# gas.net
KiCad netlist of a schematic drawn in EAGLE
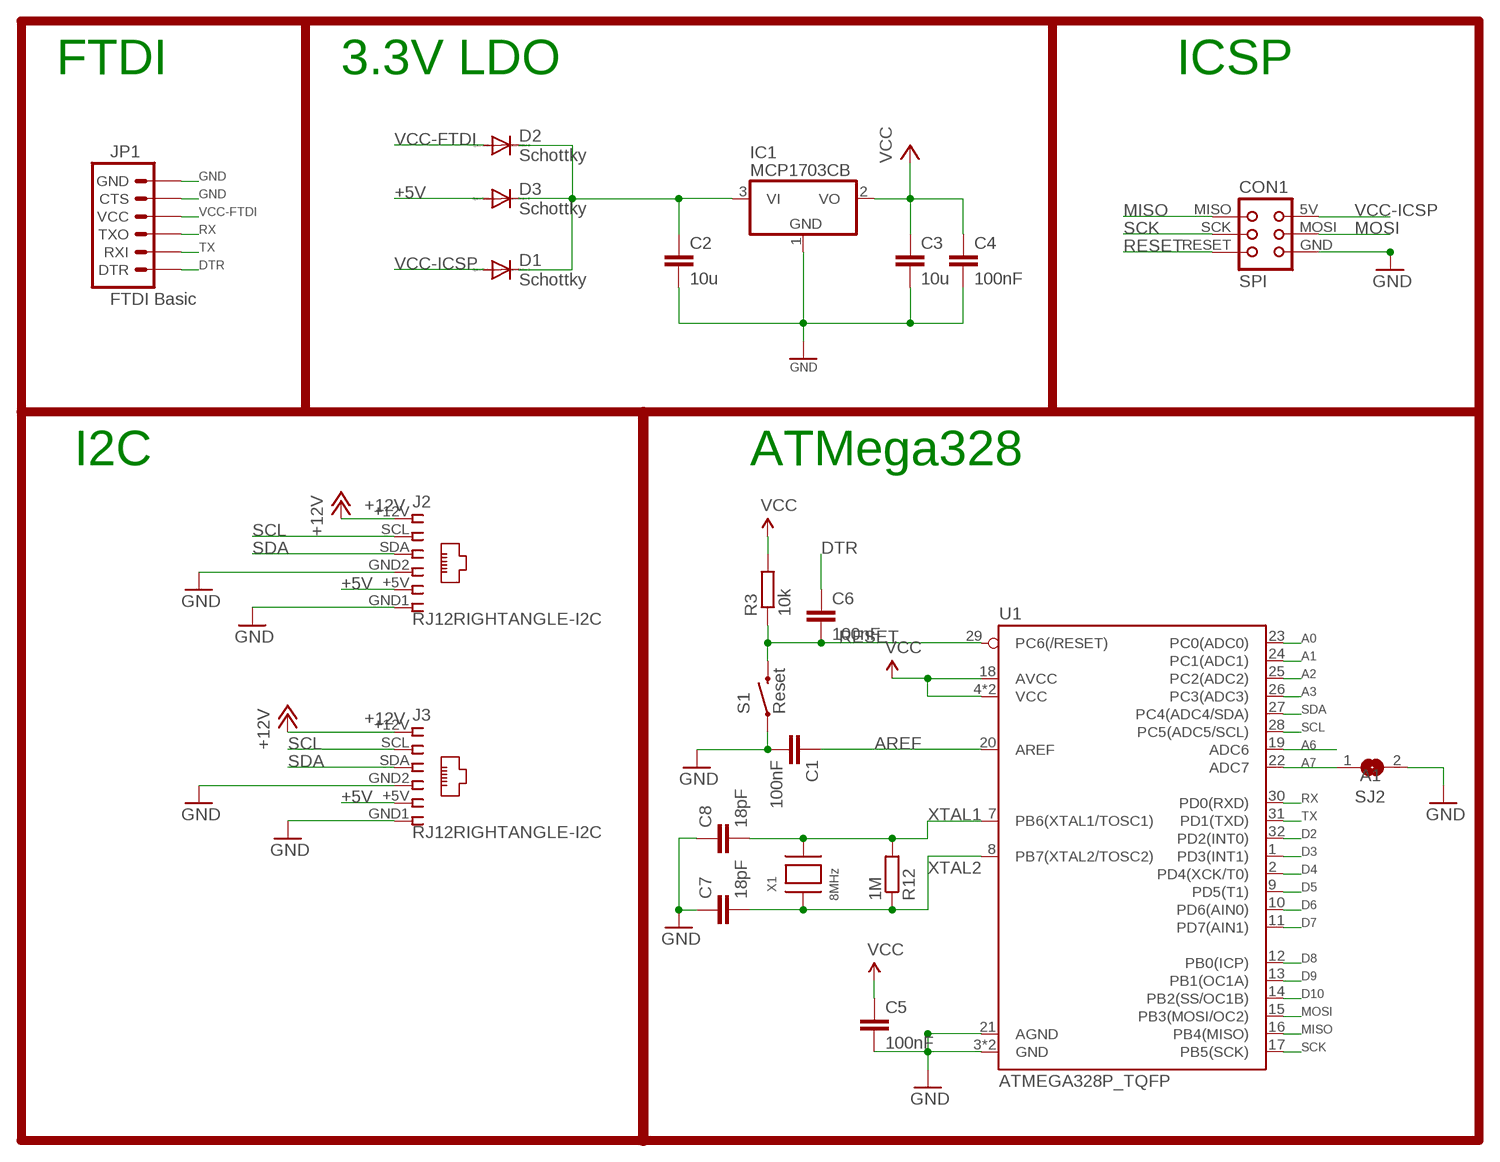
[diagram p0: schematic, sheet 1]

(export (version "E")
  (design (tool "Eeschema 10.0.6"))
  (components
    (comp (ref "C1")
      (value "100nF")
      (footprint "eagle-import:C0805K")
      (fields (field (name "MPN") "80-C1206C104K5R"))
      (libsource (lib "eagle-import") (part "C-EUC0805K"))
    )
    (comp (ref "C2")
      (value "10u")
      (footprint "eagle-import:C0805K")
      (fields (field (name "MPN") "77-VJ1206V106ZXQTBC"))
      (libsource (lib "eagle-import") (part "C-EUC0805K"))
    )
    (comp (ref "C3")
      (value "10u")
      (footprint "eagle-import:C0805K")
      (fields (field (name "MPN") "77-VJ1206V106ZXQTBC"))
      (libsource (lib "eagle-import") (part "C-EUC0805K"))
    )
    (comp (ref "C4")
      (value "100nF")
      (footprint "eagle-import:C0805K")
      (fields (field (name "MPN") "80-C1206C104K5R"))
      (libsource (lib "eagle-import") (part "C-EUC0805K"))
    )
    (comp (ref "C5")
      (value "100nF")
      (footprint "eagle-import:C0805K")
      (fields (field (name "MPN") "80-C1206C104K5R"))
      (libsource (lib "eagle-import") (part "C-EUC0805K"))
    )
    (comp (ref "C6")
      (value "100nF")
      (footprint "eagle-import:C0805K")
      (fields (field (name "MPN") "80-C1206C104K5R"))
      (libsource (lib "eagle-import") (part "C-EUC0805K"))
    )
    (comp (ref "C7")
      (value "18pF")
      (footprint "eagle-import:C0805K")
      (fields (field (name "MPN") "77-VJ1206A180JXXPBC"))
      (libsource (lib "eagle-import") (part "C-EUC0805K"))
    )
    (comp (ref "C8")
      (value "18pF")
      (footprint "eagle-import:C0805K")
      (fields (field (name "MPN") "77-VJ1206A180JXXPBC"))
      (libsource (lib "eagle-import") (part "C-EUC0805K"))
    )
    (comp (ref "CON1")
      (value "SPI")
      (footprint "eagle-import:TC2030-MCP")
      (libsource (lib "eagle-import") (part "TINYISPTAG"))
    )
    (comp (ref "D1")
      (value "Schottky")
      (footprint "eagle-import:SOD123")
      (fields (field (name "MPN") "621-1N5819HW-F"))
      (libsource (lib "eagle-import") (part "MBR0520LT"))
    )
    (comp (ref "D2")
      (value "Schottky")
      (footprint "eagle-import:SOD123")
      (fields (field (name "MPN") "621-1N5819HW-F"))
      (libsource (lib "eagle-import") (part "MBR0520LT"))
    )
    (comp (ref "D3")
      (value "Schottky")
      (footprint "eagle-import:SOD123")
      (fields (field (name "MPN") "621-1N5819HW-F"))
      (libsource (lib "eagle-import") (part "MBR0520LT"))
    )
    (comp (ref "IC1")
      (value "MCP1703CB")
      (footprint "eagle-import:SOT23")
      (libsource (lib "eagle-import") (part "MCP1703CB"))
    )
    (comp (ref "J2")
      (value "RJ12RIGHTANGLE-I2C")
      (footprint "eagle-import:RJ12-RIGHTANGLE-I2C")
      (libsource (lib "eagle-import") (part "RJ12RIGHTANGLE-I2C"))
    )
    (comp (ref "J3")
      (value "RJ12RIGHTANGLE-I2C")
      (footprint "eagle-import:RJ12-RIGHTANGLE-I2C")
      (libsource (lib "eagle-import") (part "RJ12RIGHTANGLE-I2C"))
    )
    (comp (ref "JP1")
      (value "FTDI Basic")
      (footprint "eagle-import:1X06")
      (libsource (lib "eagle-import") (part "ARDUINO_SERIAL_PROGRAMPTH"))
    )
    (comp (ref "R3")
      (value "10k")
      (footprint "eagle-import:R0805")
      (libsource (lib "eagle-import") (part "R-EU_R0805"))
    )
    (comp (ref "R12")
      (value "1M")
      (footprint "eagle-import:R0805")
      (libsource (lib "eagle-import") (part "R-EU_R0805"))
    )
    (comp (ref "S1")
      (value "Reset")
      (footprint "eagle-import:TACTILE-SWITCH-SMD-ALT01")
      (libsource (lib "eagle-import") (part "SWITCH-MOMENTARY-2SMD-ALT01"))
    )
    (comp (ref "SJ2") (value "A1") (footprint "eagle-import:SJ") (libsource (lib "eagle-import") (part "SJ")))
    (comp (ref "U1")
      (value "ATMEGA328P_TQFP")
      (footprint "eagle-import:TQFP32-08")
      (libsource (lib "eagle-import") (part "ATMEGA328P_TQFP"))
    )
    (comp (ref "X1")
      (value "8MHz")
      (footprint "eagle-import:NX6035")
      (fields (field (name "MPN") "729-F60800010"))
      (libsource (lib "eagle-import") (part "XTALNX6035"))
    )
  )
  (nets
    (net (code "1") (name "+12V") (class "Default")
      (node (ref "J2") (pin "+12V") (pinfunction "1_+12V") (pintype "bidirectional"))
      (node (ref "J3") (pin "+12V") (pinfunction "1_+12V") (pintype "bidirectional"))
    )
    (net (code "2") (name "/+5V") (class "Default")
      (node (ref "D3") (pin "A") (pinfunction "A_A") (pintype "passive"))
      (node (ref "J2") (pin "+5V") (pinfunction "5_+5V") (pintype "bidirectional"))
      (node (ref "J3") (pin "+5V") (pinfunction "5_+5V") (pintype "bidirectional"))
    )
    (net (code "3") (name "/A0") (class "Default")
      (node (ref "U1") (pin "23") (pinfunction "PC0(ADC0)_23") (pintype "bidirectional"))
    )
    (net (code "4") (name "/A1") (class "Default")
      (node (ref "U1") (pin "24") (pinfunction "PC1(ADC1)_24") (pintype "bidirectional"))
    )
    (net (code "5") (name "/A2") (class "Default")
      (node (ref "U1") (pin "25") (pinfunction "PC2(ADC2)_25") (pintype "bidirectional"))
    )
    (net (code "6") (name "/A3") (class "Default")
      (node (ref "U1") (pin "26") (pinfunction "PC3(ADC3)_26") (pintype "bidirectional"))
    )
    (net (code "7") (name "/A6") (class "Default")
      (node (ref "U1") (pin "19") (pinfunction "ADC6_19") (pintype "bidirectional"))
    )
    (net (code "8") (name "/A7") (class "Default")
      (node (ref "SJ2") (pin "1") (pinfunction "1_1") (pintype "passive"))
      (node (ref "U1") (pin "22") (pinfunction "ADC7_22") (pintype "bidirectional"))
    )
    (net (code "9") (name "/AREF") (class "Default")
      (node (ref "C1") (pin "1") (pinfunction "1_1") (pintype "passive"))
      (node (ref "U1") (pin "20") (pinfunction "AREF_20") (pintype "bidirectional"))
    )
    (net (code "10") (name "/D2") (class "Default")
      (node (ref "U1") (pin "32") (pinfunction "PD2(INT0)_32") (pintype "bidirectional"))
    )
    (net (code "11") (name "/D3") (class "Default")
      (node (ref "U1") (pin "1") (pinfunction "PD3(INT1)_1") (pintype "bidirectional"))
    )
    (net (code "12") (name "/D4") (class "Default")
      (node (ref "U1") (pin "2") (pinfunction "PD4(XCK/T0)_2") (pintype "bidirectional"))
    )
    (net (code "13") (name "/D5") (class "Default")
      (node (ref "U1") (pin "9") (pinfunction "PD5(T1)_9") (pintype "bidirectional"))
    )
    (net (code "14") (name "/D6") (class "Default")
      (node (ref "U1") (pin "10") (pinfunction "PD6(AIN0)_10") (pintype "bidirectional"))
    )
    (net (code "15") (name "/D7") (class "Default")
      (node (ref "U1") (pin "11") (pinfunction "PD7(AIN1)_11") (pintype "bidirectional"))
    )
    (net (code "16") (name "/D8") (class "Default")
      (node (ref "U1") (pin "12") (pinfunction "PB0(ICP)_12") (pintype "bidirectional"))
    )
    (net (code "17") (name "/D9") (class "Default")
      (node (ref "U1") (pin "13") (pinfunction "PB1(OC1A)_13") (pintype "bidirectional"))
    )
    (net (code "18") (name "/D10") (class "Default")
      (node (ref "U1") (pin "14") (pinfunction "PB2(SS/OC1B)_14") (pintype "bidirectional"))
    )
    (net (code "19") (name "/DTR") (class "Default")
      (node (ref "C6") (pin "1") (pinfunction "1_1") (pintype "passive"))
      (node (ref "JP1") (pin "1") (pinfunction "DTR_1") (pintype "passive"))
    )
    (net (code "20") (name "/MISO") (class "Default")
      (node (ref "CON1") (pin "MISO") (pinfunction "MISO_MISO") (pintype "passive"))
      (node (ref "U1") (pin "16") (pinfunction "PB4(MISO)_16") (pintype "bidirectional"))
    )
    (net (code "21") (name "/MOSI") (class "Default")
      (node (ref "CON1") (pin "MOSI") (pinfunction "MOSI_MOSI") (pintype "passive"))
      (node (ref "U1") (pin "15") (pinfunction "PB3(MOSI/OC2)_15") (pintype "bidirectional"))
    )
    (net (code "22") (name "/RESET") (class "Default")
      (node (ref "C6") (pin "2") (pinfunction "2_2") (pintype "passive"))
      (node (ref "CON1") (pin "RESET") (pinfunction "RESET_RESET") (pintype "passive"))
      (node (ref "R3") (pin "1") (pinfunction "1_1") (pintype "passive"))
      (node (ref "S1") (pin "3") (pinfunction "2_3") (pintype "passive"))
      (node (ref "S1") (pin "4") (pinfunction "2_4") (pintype "passive"))
      (node (ref "U1") (pin "29") (pinfunction "PC6(/RESET)_29") (pintype "bidirectional"))
    )
    (net (code "23") (name "/RX") (class "Default")
      (node (ref "JP1") (pin "3") (pinfunction "TXO_3") (pintype "passive"))
      (node (ref "U1") (pin "30") (pinfunction "PD0(RXD)_30") (pintype "bidirectional"))
    )
    (net (code "24") (name "/SCK") (class "Default")
      (node (ref "CON1") (pin "SCK") (pinfunction "SCK_SCK") (pintype "passive"))
      (node (ref "U1") (pin "17") (pinfunction "PB5(SCK)_17") (pintype "bidirectional"))
    )
    (net (code "25") (name "/SCL") (class "Default")
      (node (ref "J2") (pin "SCL") (pinfunction "2_SCL") (pintype "bidirectional"))
      (node (ref "J3") (pin "SCL") (pinfunction "2_SCL") (pintype "bidirectional"))
      (node (ref "U1") (pin "28") (pinfunction "PC5(ADC5/SCL)_28") (pintype "bidirectional"))
    )
    (net (code "26") (name "/SDA") (class "Default")
      (node (ref "J2") (pin "SDA") (pinfunction "3_SDA") (pintype "bidirectional"))
      (node (ref "J3") (pin "SDA") (pinfunction "3_SDA") (pintype "bidirectional"))
      (node (ref "U1") (pin "27") (pinfunction "PC4(ADC4/SDA)_27") (pintype "bidirectional"))
    )
    (net (code "27") (name "/TX") (class "Default")
      (node (ref "JP1") (pin "2") (pinfunction "RXI_2") (pintype "passive"))
      (node (ref "U1") (pin "31") (pinfunction "PD1(TXD)_31") (pintype "bidirectional"))
    )
    (net (code "28") (name "/VCC-FTDI") (class "Default")
      (node (ref "D2") (pin "A") (pinfunction "A_A") (pintype "passive"))
      (node (ref "JP1") (pin "4") (pinfunction "VCC_4") (pintype "passive"))
    )
    (net (code "29") (name "/VCC-ICSP") (class "Default")
      (node (ref "CON1") (pin "5V") (pinfunction "VCC_5V") (pintype "passive"))
      (node (ref "D1") (pin "A") (pinfunction "A_A") (pintype "passive"))
    )
    (net (code "30") (name "/XTAL1") (class "Default")
      (node (ref "C8") (pin "2") (pinfunction "2_2") (pintype "passive"))
      (node (ref "R12") (pin "2") (pinfunction "2_2") (pintype "passive"))
      (node (ref "U1") (pin "7") (pinfunction "PB6(XTAL1/TOSC1)_7") (pintype "bidirectional"))
      (node (ref "X1") (pin "P$2") (pinfunction "P$2_P$2") (pintype "bidirectional"))
    )
    (net (code "31") (name "/XTAL2") (class "Default")
      (node (ref "C7") (pin "2") (pinfunction "2_2") (pintype "passive"))
      (node (ref "R12") (pin "1") (pinfunction "1_1") (pintype "passive"))
      (node (ref "U1") (pin "8") (pinfunction "PB7(XTAL2/TOSC2)_8") (pintype "bidirectional"))
      (node (ref "X1") (pin "P$1") (pinfunction "P$1_P$1") (pintype "bidirectional"))
    )
    (net (code "32") (name "GND") (class "Default")
      (node (ref "C1") (pin "2") (pinfunction "2_2") (pintype "passive"))
      (node (ref "C2") (pin "2") (pinfunction "2_2") (pintype "passive"))
      (node (ref "C3") (pin "2") (pinfunction "2_2") (pintype "passive"))
      (node (ref "C4") (pin "2") (pinfunction "2_2") (pintype "passive"))
      (node (ref "C5") (pin "2") (pinfunction "2_2") (pintype "passive"))
      (node (ref "C7") (pin "1") (pinfunction "1_1") (pintype "passive"))
      (node (ref "C8") (pin "1") (pinfunction "1_1") (pintype "passive"))
      (node (ref "CON1") (pin "GND") (pinfunction "GND_GND") (pintype "passive"))
      (node (ref "IC1") (pin "1") (pinfunction "GND_1") (pintype "passive"))
      (node (ref "J2") (pin "GND1") (pinfunction "6_GND1") (pintype "bidirectional"))
      (node (ref "J2") (pin "GND2") (pinfunction "4_GND2") (pintype "bidirectional"))
      (node (ref "J3") (pin "GND1") (pinfunction "6_GND1") (pintype "bidirectional"))
      (node (ref "J3") (pin "GND2") (pinfunction "4_GND2") (pintype "bidirectional"))
      (node (ref "JP1") (pin "5") (pinfunction "CTS_5") (pintype "passive"))
      (node (ref "JP1") (pin "6") (pinfunction "GND_6") (pintype "passive"))
      (node (ref "S1") (pin "1") (pinfunction "1_1") (pintype "passive"))
      (node (ref "S1") (pin "2") (pinfunction "1_2") (pintype "passive"))
      (node (ref "SJ2") (pin "2") (pinfunction "2_2") (pintype "passive"))
      (node (ref "U1") (pin "21") (pinfunction "AGND_21") (pintype "bidirectional"))
      (node (ref "U1") (pin "3") (pinfunction "GND_3") (pintype "bidirectional"))
      (node (ref "U1") (pin "5") (pinfunction "GND_5") (pintype "bidirectional"))
    )
    (net (code "33") (name "Net-(IC1-VI)") (class "Default")
      (node (ref "C2") (pin "1") (pinfunction "1_1") (pintype "passive"))
      (node (ref "D1") (pin "C") (pinfunction "C_C") (pintype "passive"))
      (node (ref "D2") (pin "C") (pinfunction "C_C") (pintype "passive"))
      (node (ref "D3") (pin "C") (pinfunction "C_C") (pintype "passive"))
      (node (ref "IC1") (pin "3") (pinfunction "VI_3") (pintype "input"))
    )
    (net (code "34") (name "VCC") (class "Default")
      (node (ref "C3") (pin "1") (pinfunction "1_1") (pintype "passive"))
      (node (ref "C4") (pin "1") (pinfunction "1_1") (pintype "passive"))
      (node (ref "C5") (pin "1") (pinfunction "1_1") (pintype "passive"))
      (node (ref "IC1") (pin "2") (pinfunction "VO_2") (pintype "passive"))
      (node (ref "R3") (pin "2") (pinfunction "2_2") (pintype "passive"))
      (node (ref "U1") (pin "18") (pinfunction "AVCC_18") (pintype "bidirectional"))
      (node (ref "U1") (pin "4") (pinfunction "VCC_4") (pintype "bidirectional"))
      (node (ref "U1") (pin "6") (pinfunction "VCC_6") (pintype "bidirectional"))
    )
  )
)
